# Alimentation_USB_Header.net
KiCad netlist of a schematic drawn in Altium Designer
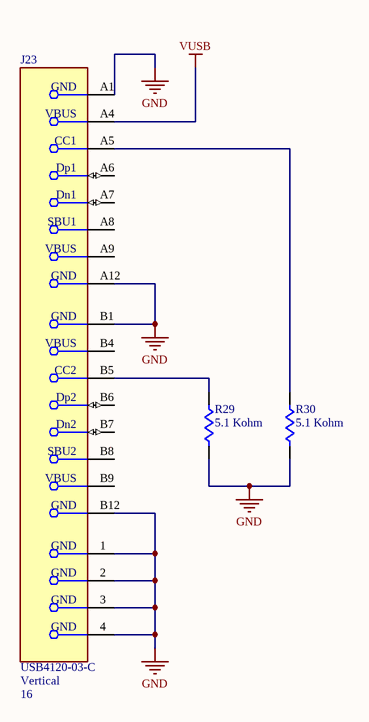
[diagram p0: Alimentation_USB_Header.SchDoc]

(export (version "E")
  (design (tool "Eeschema 10.0.6"))
  (components
    (comp (ref "J23")
      (value "USB4120-03-C")
      (footprint "FP-USB4120-03-C-MFG")
      (description "USB4120-03-C 16 Position 48 VDC USB Type C Vertical USB 2.0 Receptacle Connector")
      (fields (field (name "ORIENTATION") "Vertical") (field (name "NUMBER OF PINS") "16"))
      (libsource (lib "Altium Content Vault") (part "7d1897e331a05e41f957c7eb139585a"))
    )
    (comp (ref "R29")
      (value "5.1 Kohm")
      (footprint "Res_Template")
      (description "Custom Semiconductor Resistor")
      (libsource (lib "Schlib1") (part "470 ohm"))
    )
    (comp (ref "R30")
      (value "5.1 Kohm")
      (footprint "Res_Template")
      (description "Custom Semiconductor Resistor")
      (libsource (lib "Schlib1") (part "470 ohm"))
    )
  )
  (nets
    (net (code "1") (name "GND") (class "Default")
      (node (ref "J23") (pin "1") (pinfunction "GND_1") (pintype "power_in"))
      (node (ref "J23") (pin "2") (pinfunction "GND_2") (pintype "power_in"))
      (node (ref "J23") (pin "3") (pinfunction "GND_3") (pintype "power_in"))
      (node (ref "J23") (pin "4") (pinfunction "GND_4") (pintype "power_in"))
      (node (ref "J23") (pin "A1") (pinfunction "GND_A1") (pintype "power_in"))
      (node (ref "J23") (pin "A12") (pinfunction "GND_A12") (pintype "power_in"))
      (node (ref "J23") (pin "B1") (pinfunction "GND_B1") (pintype "power_in"))
      (node (ref "J23") (pin "B12") (pinfunction "GND_B12") (pintype "power_in"))
      (node (ref "R29") (pin "1") (pinfunction "1_1") (pintype "passive"))
      (node (ref "R30") (pin "1") (pinfunction "1_1") (pintype "passive"))
    )
    (net (code "2") (name "Net-(J23-CC1)") (class "Default")
      (node (ref "J23") (pin "A5") (pinfunction "CC1_A5") (pintype "passive"))
      (node (ref "R30") (pin "2") (pinfunction "2_2") (pintype "passive"))
    )
    (net (code "3") (name "Net-(J23-CC2)") (class "Default")
      (node (ref "J23") (pin "B5") (pinfunction "CC2_B5") (pintype "passive"))
      (node (ref "R29") (pin "2") (pinfunction "2_2") (pintype "passive"))
    )
    (net (code "4") (name "VUSB") (class "Default")
      (node (ref "J23") (pin "A4") (pinfunction "VBUS_A4") (pintype "power_in"))
    )
    (net (code "5") (name "unconnected-(J23-Dn1-PadA7)") (class "Default")
      (node (ref "J23") (pin "A7") (pinfunction "Dn1_A7") (pintype "bidirectional"))
    )
    (net (code "6") (name "unconnected-(J23-Dn2-PadB7)") (class "Default")
      (node (ref "J23") (pin "B7") (pinfunction "Dn2_B7") (pintype "bidirectional"))
    )
    (net (code "7") (name "unconnected-(J23-Dp1-PadA6)") (class "Default")
      (node (ref "J23") (pin "A6") (pinfunction "Dp1_A6") (pintype "bidirectional"))
    )
    (net (code "8") (name "unconnected-(J23-Dp2-PadB6)") (class "Default")
      (node (ref "J23") (pin "B6") (pinfunction "Dp2_B6") (pintype "bidirectional"))
    )
    (net (code "9") (name "unconnected-(J23-SBU1-PadA8)") (class "Default")
      (node (ref "J23") (pin "A8") (pinfunction "SBU1_A8") (pintype "passive"))
    )
    (net (code "10") (name "unconnected-(J23-SBU2-PadB8)") (class "Default")
      (node (ref "J23") (pin "B8") (pinfunction "SBU2_B8") (pintype "passive"))
    )
    (net (code "11") (name "unconnected-(J23-VBUS-PadA9)") (class "Default")
      (node (ref "J23") (pin "A9") (pinfunction "VBUS_A9") (pintype "power_in"))
    )
    (net (code "12") (name "unconnected-(J23-VBUS-PadB4)") (class "Default")
      (node (ref "J23") (pin "B4") (pinfunction "VBUS_B4") (pintype "power_in"))
    )
    (net (code "13") (name "unconnected-(J23-VBUS-PadB9)") (class "Default")
      (node (ref "J23") (pin "B9") (pinfunction "VBUS_B9") (pintype "power_in"))
    )
  )
)
